# FU6561N-XCQ-DEMO_V1_0-20251116.net
KiCad netlist of a schematic drawn in Altium Designer
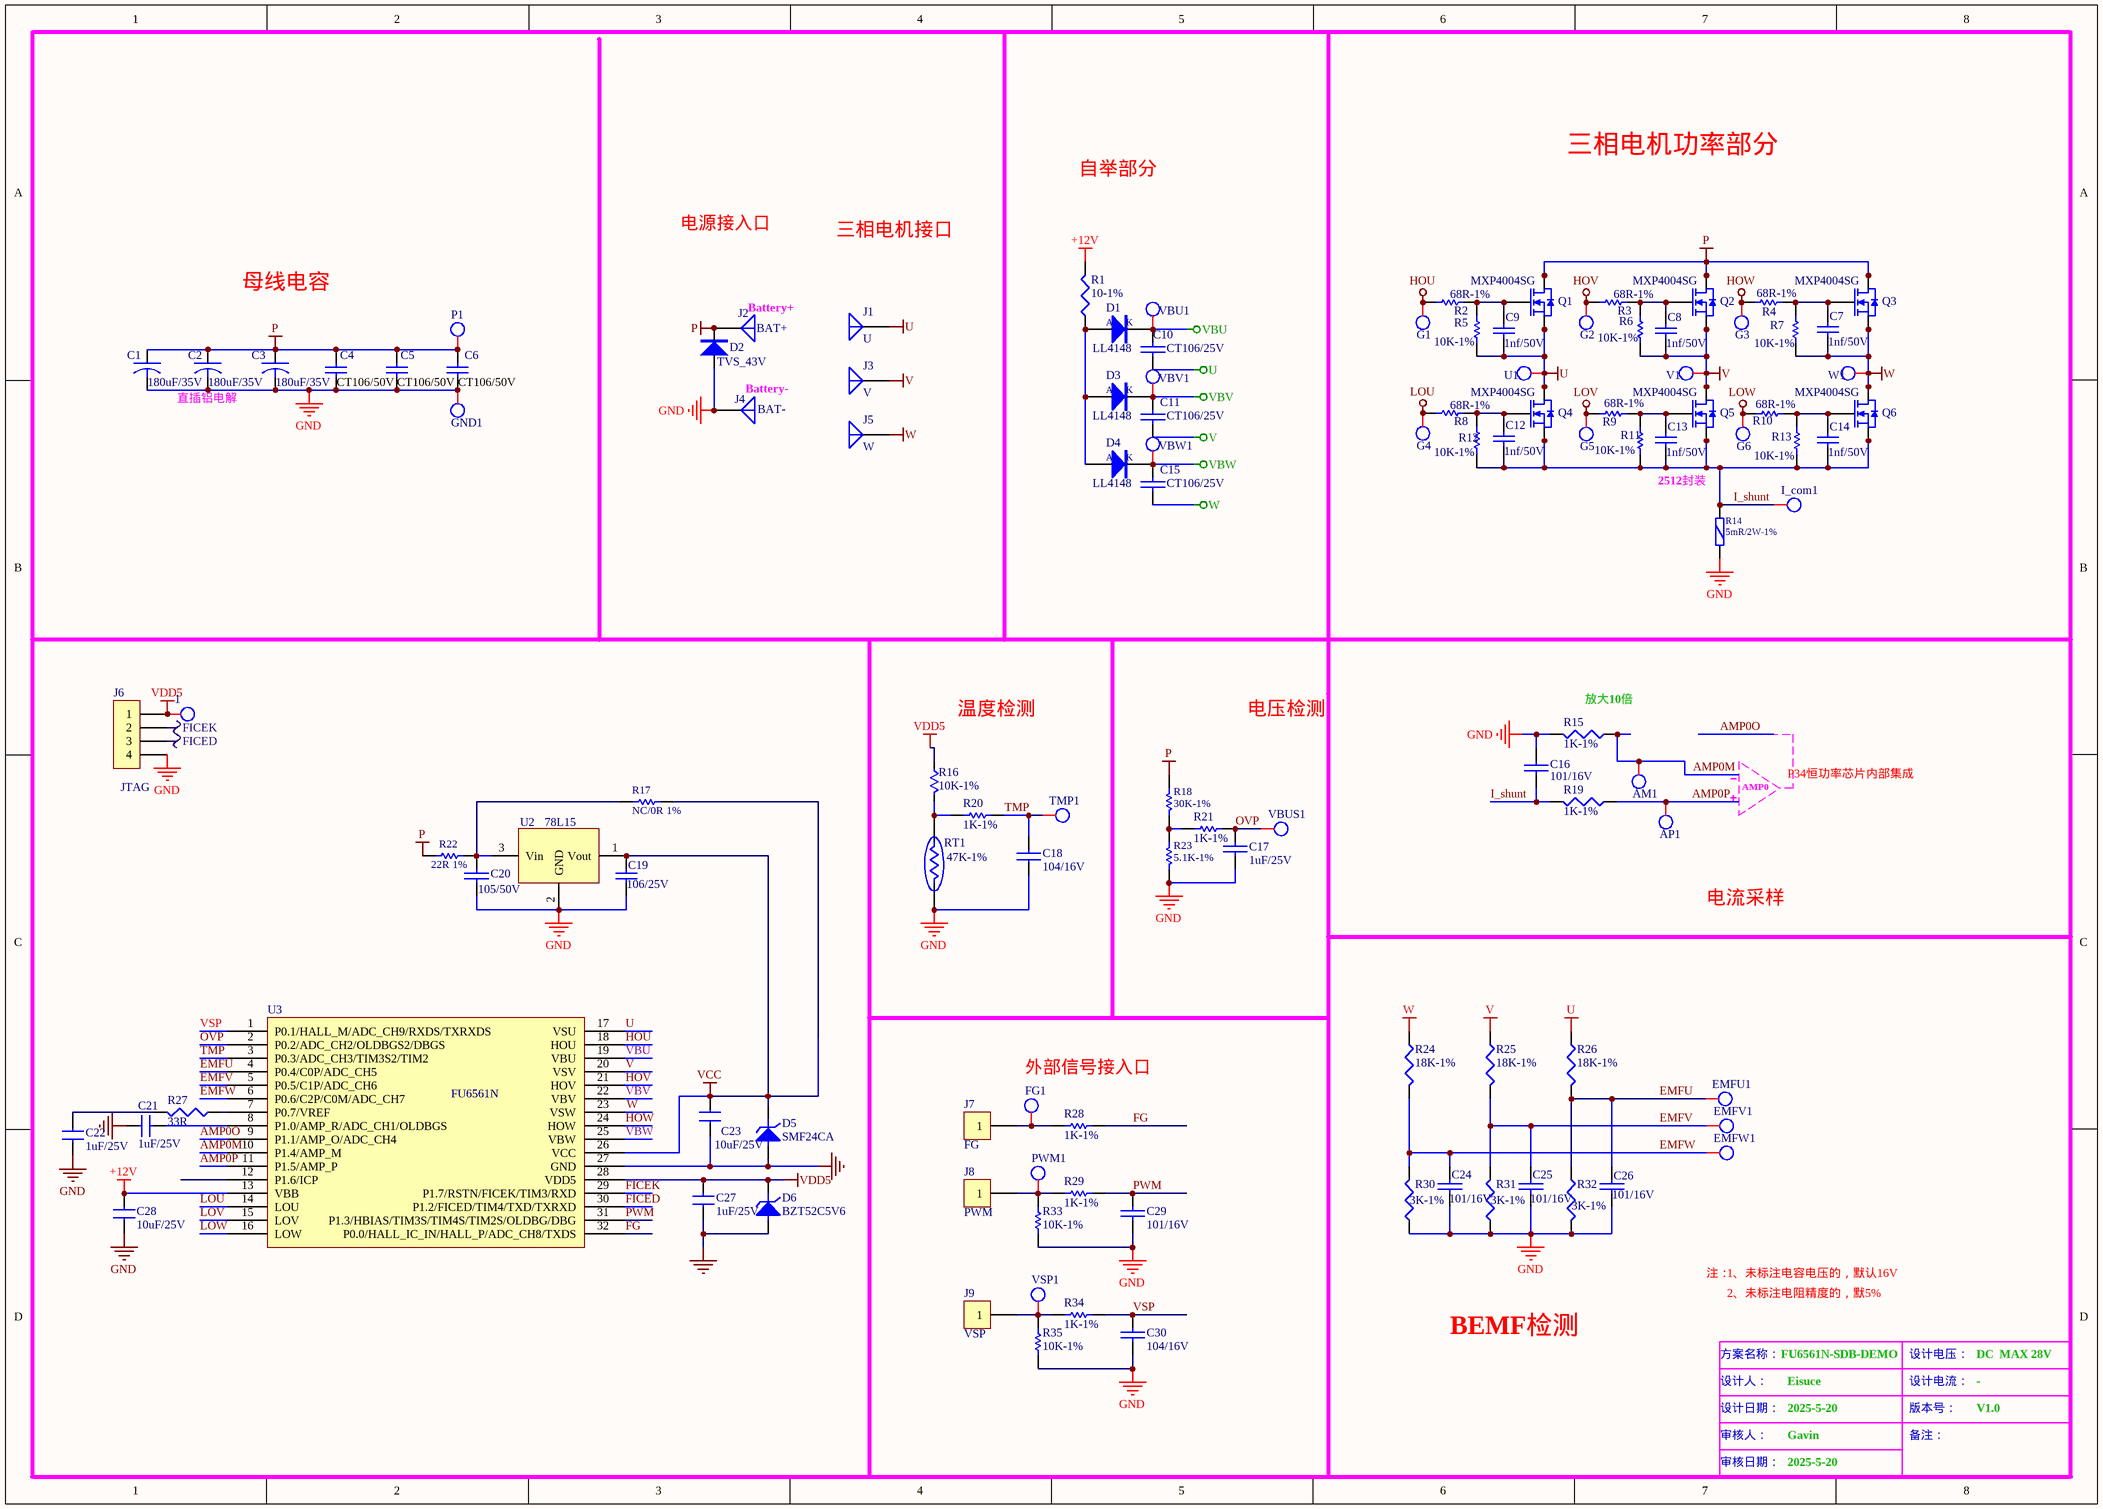
[diagram p0: FU6561N-XCQ-DEMO_V1.0-20251116.SCHDOC]

(export (version "E")
  (design (tool "Eeschema 10.0.6"))
  (components
    (comp (ref "1") (value "~") (footprint "TPM") (libsource (lib "*") (part "Component_1")))
    (comp (ref "AM1") (value "~") (footprint "TPM") (libsource (lib "*") (part "Component_1")))
    (comp (ref "AP1") (value "~") (footprint "TPM") (libsource (lib "*") (part "Component_1")))
    (comp (ref "C1")
      (value "180uF/35V")
      (footprint "CAP2_5")
      (description "Capacitor")
      (libsource (lib "*") (part "CAPACITOR"))
    )
    (comp (ref "C2")
      (value "180uF/35V")
      (footprint "CAP2_5")
      (description "Capacitor")
      (libsource (lib "*") (part "CAPACITOR"))
    )
    (comp (ref "C3")
      (value "180uF/35V")
      (footprint "CAP2_5")
      (description "Capacitor")
      (libsource (lib "*") (part "CAPACITOR"))
    )
    (comp (ref "C4")
      (value "CT106/50V")
      (footprint "c1206")
      (description "YG-C1206K106-50V（10UF）-10%")
      (fields (field (name "PUBLISHER") "Altium Limited"))
      (libsource (lib "*") (part "Cap"))
    )
    (comp (ref "C5")
      (value "CT106/50V")
      (footprint "c1206")
      (description "YG-C1206K106-50V（10UF）-10%")
      (fields (field (name "PUBLISHER") "Altium Limited"))
      (libsource (lib "*") (part "Cap"))
    )
    (comp (ref "C6")
      (value "CT106/50V")
      (footprint "c1206")
      (description "YG-C1206K106-50V（10UF）-10%")
      (fields (field (name "PUBLISHER") "Altium Limited"))
      (libsource (lib "*") (part "Cap"))
    )
    (comp (ref "C7")
      (value "1nf/50V")
      (footprint "c0603")
      (description "YG-C1206K106-50V（10UF）-10%")
      (fields (field (name "PUBLISHER") "Altium Limited"))
      (libsource (lib "*") (part "Cap"))
    )
    (comp (ref "C8")
      (value "1nf/50V")
      (footprint "C0603")
      (description "YG-C1206K106-50V（10UF）-10%")
      (fields (field (name "PUBLISHER") "Altium Limited"))
      (libsource (lib "*") (part "Cap"))
    )
    (comp (ref "C9")
      (value "1nf/50V")
      (footprint "C0603")
      (description "YG-C1206K106-50V（10UF）-10%")
      (fields (field (name "PUBLISHER") "Altium Limited"))
      (libsource (lib "*") (part "Cap"))
    )
    (comp (ref "C10")
      (value "CT106/25V")
      (footprint "c0805")
      (description "Capacitor")
      (libsource (lib "*") (part "CAP-CC(SMD)"))
    )
    (comp (ref "C11")
      (value "CT106/25V")
      (footprint "c0805")
      (description "Capacitor")
      (libsource (lib "*") (part "CAP-CC(SMD)"))
    )
    (comp (ref "C12")
      (value "1nf/50V")
      (footprint "c0603")
      (description "YG-C1206K106-50V（10UF）-10%")
      (fields (field (name "PUBLISHER") "Altium Limited"))
      (libsource (lib "*") (part "Cap"))
    )
    (comp (ref "C13")
      (value "1nf/50V")
      (footprint "C0603")
      (description "YG-C1206K106-50V（10UF）-10%")
      (fields (field (name "PUBLISHER") "Altium Limited"))
      (libsource (lib "*") (part "Cap"))
    )
    (comp (ref "C14")
      (value "1nf/50V")
      (footprint "C0603")
      (description "YG-C1206K106-50V（10UF）-10%")
      (fields (field (name "PUBLISHER") "Altium Limited"))
      (libsource (lib "*") (part "Cap"))
    )
    (comp (ref "C15")
      (value "CT106/25V")
      (footprint "c0805")
      (description "Capacitor")
      (libsource (lib "*") (part "CAP-CC(SMD)"))
    )
    (comp (ref "C16")
      (value "101/16V")
      (footprint "c0603")
      (description "Capacitor")
      (libsource (lib "") (part "CAP_1"))
    )
    (comp (ref "C17")
      (value "1uF/25V")
      (footprint "c0603")
      (description "Capacitor")
      (libsource (lib "") (part "CAP_2"))
    )
    (comp (ref "C18") (value "104/16V") (footprint "c0603") (libsource (lib "*") (part "CAP NP")))
    (comp (ref "C19")
      (value "106/25V")
      (footprint "C0805")
      (description "Capacitor (Semiconductor SIM Model)")
      (fields (field (name "PUBLISHER") "Altium Limited"))
      (libsource (lib "Miscellaneous Devices") (part "Cap Semi"))
    )
    (comp (ref "C20")
      (value "105/50V")
      (footprint "c1206")
      (description "Capacitor")
      (libsource (lib "") (part "CAP_2"))
    )
    (comp (ref "C21")
      (value "1uF/25V")
      (footprint "C0603")
      (description "Capacitor")
      (libsource (lib "*") (part "CAP"))
    )
    (comp (ref "C22")
      (value "1uF/25V")
      (footprint "C0603")
      (description "Capacitor")
      (libsource (lib "*") (part "CAP"))
    )
    (comp (ref "C23")
      (value "10uF/25V")
      (footprint "C0603")
      (description "Capacitor")
      (libsource (lib "*") (part "CAP"))
    )
    (comp (ref "C24")
      (value "101/16V")
      (footprint "c0603")
      (description "Capacitor")
      (libsource (lib "") (part "CAP_1"))
    )
    (comp (ref "C25")
      (value "101/16V")
      (footprint "c0603")
      (description "Capacitor")
      (libsource (lib "") (part "CAP_1"))
    )
    (comp (ref "C26")
      (value "101/16V")
      (footprint "c0603")
      (description "Capacitor")
      (libsource (lib "") (part "CAP_1"))
    )
    (comp (ref "C27")
      (value "1uF/25V")
      (footprint "C0603")
      (description "Capacitor")
      (libsource (lib "*") (part "CAP"))
    )
    (comp (ref "C28")
      (value "10uF/25V")
      (footprint "C0603")
      (description "Capacitor")
      (libsource (lib "*") (part "CAP"))
    )
    (comp (ref "C29")
      (value "101/16V")
      (footprint "c0603")
      (description "Capacitor")
      (libsource (lib "") (part "CAP_2"))
    )
    (comp (ref "C30")
      (value "104/16V")
      (footprint "c0603")
      (description "Capacitor")
      (libsource (lib "") (part "CAP_2"))
    )
    (comp (ref "D1")
      (value "LL4148")
      (footprint "SOD-123")
      (description "Diode")
      (libsource (lib "*") (part "DIODE"))
    )
    (comp (ref "D2") (value "TVS_43V") (footprint "DO214AA, SMB") (libsource (lib "*") (part "D1206")))
    (comp (ref "D3")
      (value "LL4148")
      (footprint "SOD-123")
      (description "Diode")
      (libsource (lib "*") (part "DIODE"))
    )
    (comp (ref "D4")
      (value "LL4148")
      (footprint "SOD-123")
      (description "Diode")
      (libsource (lib "*") (part "DIODE"))
    )
    (comp (ref "D5")
      (value "SMF24CA")
      (footprint "SOD-123")
      (description "Zener Diode")
      (libsource (lib "") (part "TVS1_1"))
    )
    (comp (ref "D6")
      (value "BZT52C5V6")
      (footprint "SOD-123")
      (description "Zener Diode")
      (libsource (lib "*") (part "TVS1"))
    )
    (comp (ref "EMFU1") (value "~") (footprint "TPM") (libsource (lib "*") (part "Component_1")))
    (comp (ref "EMFV1") (value "~") (footprint "TPM") (libsource (lib "*") (part "Component_1")))
    (comp (ref "EMFW1") (value "~") (footprint "TPM") (libsource (lib "*") (part "Component_1")))
    (comp (ref "FG1") (value "~") (footprint "TPM") (libsource (lib "*") (part "Component_1")))
    (comp (ref "G1") (value "~") (footprint "TPM") (libsource (lib "*") (part "Component_1")))
    (comp (ref "G2") (value "~") (footprint "TPM") (libsource (lib "*") (part "Component_1")))
    (comp (ref "G3") (value "~") (footprint "TPM") (libsource (lib "*") (part "Component_1")))
    (comp (ref "G4") (value "~") (footprint "TPM") (libsource (lib "*") (part "Component_1")))
    (comp (ref "G5") (value "~") (footprint "TPM") (libsource (lib "*") (part "Component_1")))
    (comp (ref "G6") (value "~") (footprint "TPM") (libsource (lib "*") (part "Component_1")))
    (comp (ref "GND1") (value "~") (footprint "TPM") (libsource (lib "*") (part "Component_1")))
    (comp (ref "I_com1") (value "~") (footprint "TPM") (libsource (lib "*") (part "Component_1")))
    (comp (ref "J1")
      (value "U")
      (footprint "AD")
      (description "Generic Antenna")
      (libsource (lib "*") (part "ANTENNA"))
    )
    (comp (ref "J2")
      (value "BAT+")
      (footprint "DY")
      (description "Generic Antenna")
      (libsource (lib "") (part "ANTENNA_2"))
    )
    (comp (ref "J3")
      (value "V")
      (footprint "AD")
      (description "Generic Antenna")
      (libsource (lib "") (part "ANTENNA_3"))
    )
    (comp (ref "J4")
      (value "BAT-")
      (footprint "DY")
      (description "Generic Antenna")
      (libsource (lib "") (part "ANTENNA_2"))
    )
    (comp (ref "J5")
      (value "W")
      (footprint "AD")
      (description "Generic Antenna")
      (libsource (lib "") (part "ANTENNA_1"))
    )
    (comp (ref "J6")
      (value "JTAG")
      (footprint "SIP4-2")
      (description "Connector")
      (libsource (lib "*") (part "CON4"))
    )
    (comp (ref "J7")
      (value "FG")
      (footprint "tp")
      (description "Connector")
      (libsource (lib "SCH 常用封装") (part "CON1"))
    )
    (comp (ref "J8")
      (value "PWM")
      (footprint "tp")
      (description "Connector")
      (libsource (lib "SCH 常用封装") (part "CON1"))
    )
    (comp (ref "J9")
      (value "VSP")
      (footprint "tp")
      (description "Connector")
      (libsource (lib "SCH 常用封装") (part "CON1"))
    )
    (comp (ref "P1") (value "~") (footprint "TPM") (libsource (lib "*") (part "Component_1")))
    (comp (ref "PWM1") (value "~") (footprint "TPM") (libsource (lib "*") (part "Component_1")))
    (comp (ref "Q1") (value "MXP4004SG") (footprint "PQFQ5X6") (libsource (lib "*") (part "MOSFET-N")))
    (comp (ref "Q2") (value "MXP4004SG") (footprint "PQFQ5X6") (libsource (lib "*") (part "MOSFET-N")))
    (comp (ref "Q3") (value "MXP4004SG") (footprint "PQFQ5X6") (libsource (lib "*") (part "MOSFET-N")))
    (comp (ref "Q4") (value "MXP4004SG") (footprint "PQFQ5X6") (libsource (lib "*") (part "MOSFET-N")))
    (comp (ref "Q5") (value "MXP4004SG") (footprint "PQFQ5X6") (libsource (lib "*") (part "MOSFET-N")))
    (comp (ref "Q6") (value "MXP4004SG") (footprint "PQFQ5X6") (libsource (lib "*") (part "MOSFET-N")))
    (comp (ref "R1") (value "10-1%") (footprint "r1206") (libsource (lib "*") (part "RES(SMD)")))
    (comp (ref "R2")
      (value "68R-1%")
      (footprint "r0603")
      (description "Semiconductor Resistor")
      (fields (field (name "PUBLISHER") "Altium Limited"))
      (libsource (lib "Miscellaneous Devices") (part "Res Semi"))
    )
    (comp (ref "R3")
      (value "68R-1%")
      (footprint "r0603")
      (description "Semiconductor Resistor")
      (fields (field (name "PUBLISHER") "Altium Limited"))
      (libsource (lib "Miscellaneous Devices") (part "Res Semi"))
    )
    (comp (ref "R4")
      (value "68R-1%")
      (footprint "r0603")
      (description "Semiconductor Resistor")
      (fields (field (name "PUBLISHER") "Altium Limited"))
      (libsource (lib "Miscellaneous Devices") (part "Res Semi"))
    )
    (comp (ref "R5")
      (value "10K-1%")
      (footprint "r0603")
      (description "YG-R0603F2002(20KΩ)-1%")
      (fields (field (name "PUBLISHER") "Altium Limited"))
      (libsource (lib "Miscellaneous Devices") (part "Res Semi"))
    )
    (comp (ref "R6")
      (value "10K-1%")
      (footprint "r0603")
      (description "YG-R0603F2002(20KΩ)-1%")
      (fields (field (name "PUBLISHER") "Altium Limited"))
      (libsource (lib "Miscellaneous Devices") (part "Res Semi"))
    )
    (comp (ref "R7")
      (value "10K-1%")
      (footprint "r0603")
      (description "YG-R0603F2002(20KΩ)-1%")
      (fields (field (name "PUBLISHER") "Altium Limited"))
      (libsource (lib "Miscellaneous Devices") (part "Res Semi"))
    )
    (comp (ref "R8")
      (value "68R-1%")
      (footprint "r0603")
      (description "Semiconductor Resistor")
      (fields (field (name "PUBLISHER") "Altium Limited"))
      (libsource (lib "Miscellaneous Devices") (part "Res Semi"))
    )
    (comp (ref "R9")
      (value "68R-1%")
      (footprint "r0603")
      (description "Semiconductor Resistor")
      (fields (field (name "PUBLISHER") "Altium Limited"))
      (libsource (lib "Miscellaneous Devices") (part "Res Semi"))
    )
    (comp (ref "R10")
      (value "68R-1%")
      (footprint "r0603")
      (description "Semiconductor Resistor")
      (fields (field (name "PUBLISHER") "Altium Limited"))
      (libsource (lib "Miscellaneous Devices") (part "Res Semi"))
    )
    (comp (ref "R11")
      (value "10K-1%")
      (footprint "r0603")
      (description "YG-R0603F2002(20KΩ)-1%")
      (fields (field (name "PUBLISHER") "Altium Limited"))
      (libsource (lib "Miscellaneous Devices") (part "Res Semi"))
    )
    (comp (ref "R12")
      (value "10K-1%")
      (footprint "r0603")
      (description "YG-R0603F2002(20KΩ)-1%")
      (fields (field (name "PUBLISHER") "Altium Limited"))
      (libsource (lib "Miscellaneous Devices") (part "Res Semi"))
    )
    (comp (ref "R13")
      (value "10K-1%")
      (footprint "r0603")
      (description "YG-R0603F2002(20KΩ)-1%")
      (fields (field (name "PUBLISHER") "Altium Limited"))
      (libsource (lib "Miscellaneous Devices") (part "Res Semi"))
    )
    (comp (ref "R14") (value "5mR/2W-1%") (footprint "r2512") (libsource (lib "*") (part "R-RES/2")))
    (comp (ref "R15") (value "1K-1%") (footprint "r0603") (libsource (lib "*") (part "RES(SMD)")))
    (comp (ref "R16") (value "10K-1%") (footprint "r0603") (libsource (lib "*") (part "RES3")))
    (comp (ref "R17")
      (value "NC/0R 1%")
      (footprint "R1206")
      (description "R0603F1001(1KΩ)-1%")
      (fields (field (name "PUBLISHER") "Altium Limited"))
      (libsource (lib "Miscellaneous Devices") (part "res1"))
    )
    (comp (ref "R18")
      (value "30K-1%")
      (footprint "r0603")
      (description "Resistor")
      (fields (field (name "PUBLISHER") "Altium Limited"))
      (libsource (lib "Miscellaneous Devices") (part "res1"))
    )
    (comp (ref "R19") (value "1K-1%") (footprint "r0603") (libsource (lib "*") (part "RES(SMD)")))
    (comp (ref "R20")
      (value "1K-1%")
      (footprint "r0603")
      (description "Semiconductor Resistor")
      (fields (field (name "PUBLISHER") "Altium Limited"))
      (libsource (lib "Miscellaneous Devices") (part "Res Semi"))
    )
    (comp (ref "R21")
      (value "1K-1%")
      (footprint "r0603")
      (description "Semiconductor Resistor")
      (fields (field (name "PUBLISHER") "Altium Limited"))
      (libsource (lib "Miscellaneous Devices") (part "Res Semi"))
    )
    (comp (ref "R22")
      (value "22R 1%")
      (footprint "R1206")
      (description "R0603F1001(1KΩ)-1%")
      (fields (field (name "PUBLISHER") "Altium Limited"))
      (libsource (lib "Miscellaneous Devices") (part "res1"))
    )
    (comp (ref "R23")
      (value "5.1K-1%")
      (footprint "r0603")
      (description "Resistor")
      (fields (field (name "PUBLISHER") "Altium Limited"))
      (libsource (lib "Miscellaneous Devices") (part "res1"))
    )
    (comp (ref "R24") (value "18K-1%") (footprint "r0603") (libsource (lib "*") (part "RES(SMD)")))
    (comp (ref "R25") (value "18K-1%") (footprint "r0603") (libsource (lib "*") (part "RES(SMD)")))
    (comp (ref "R26") (value "18K-1%") (footprint "r0603") (libsource (lib "*") (part "RES(SMD)")))
    (comp (ref "R27") (value "33R") (footprint "R0603") (libsource (lib "*") (part "RES(SMD)")))
    (comp (ref "R28")
      (value "1K-1%")
      (footprint "r0603")
      (description "Semiconductor Resistor")
      (fields (field (name "PUBLISHER") "Altium Limited"))
      (libsource (lib "Miscellaneous Devices") (part "Res Semi"))
    )
    (comp (ref "R29")
      (value "1K-1%")
      (footprint "r0603")
      (description "Semiconductor Resistor")
      (fields (field (name "PUBLISHER") "Altium Limited"))
      (libsource (lib "Miscellaneous Devices") (part "Res Semi"))
    )
    (comp (ref "R30") (value "3K-1%") (footprint "r0603") (libsource (lib "*") (part "RES(SMD)")))
    (comp (ref "R31") (value "3K-1%") (footprint "r0603") (libsource (lib "*") (part "RES(SMD)")))
    (comp (ref "R32") (value "3K-1%") (footprint "r0603") (libsource (lib "*") (part "RES(SMD)")))
    (comp (ref "R33")
      (value "10K-1%")
      (footprint "r0603")
      (description "Semiconductor Resistor")
      (fields (field (name "PUBLISHER") "Altium Limited"))
      (libsource (lib "Miscellaneous Devices") (part "Res Semi"))
    )
    (comp (ref "R34")
      (value "1K-1%")
      (footprint "r0603")
      (description "Semiconductor Resistor")
      (fields (field (name "PUBLISHER") "Altium Limited"))
      (libsource (lib "Miscellaneous Devices") (part "Res Semi"))
    )
    (comp (ref "R35")
      (value "10K-1%")
      (footprint "r0603")
      (description "Semiconductor Resistor")
      (fields (field (name "PUBLISHER") "Altium Limited"))
      (libsource (lib "Miscellaneous Devices") (part "Res Semi"))
    )
    (comp (ref "RT1")
      (value "47K-1%")
      (footprint "r0603")
      (description "Thermistor")
      (fields (field (name "PUBLISHER") "Altium Limited"))
      (libsource (lib "*") (part "Res Thermal"))
    )
    (comp (ref "TMP1") (value "~") (footprint "TPM") (libsource (lib "*") (part "Component_1")))
    (comp (ref "U1") (value "~") (footprint "TPM") (libsource (lib "*") (part "Component_1")))
    (comp (ref "U2")
      (value "78L15")
      (footprint "SOT-89")
      (description "78M12")
      (libsource (lib "*") (part "VOLTREG"))
    )
    (comp (ref "U3")
      (value "FU6561N")
      (footprint "QFN32-0.4-4X4")
      (libsource (lib "SCH 常用封装") (part "FU6561N"))
    )
    (comp (ref "V1") (value "~") (footprint "TPM") (libsource (lib "*") (part "Component_1")))
    (comp (ref "VBU1") (value "~") (footprint "TPM") (libsource (lib "*") (part "Component_1")))
    (comp (ref "VBUS1") (value "~") (footprint "TPM") (libsource (lib "*") (part "Component_1")))
    (comp (ref "VBV1") (value "~") (footprint "TPM") (libsource (lib "*") (part "Component_1")))
    (comp (ref "VBW1") (value "~") (footprint "TPM") (libsource (lib "*") (part "Component_1")))
    (comp (ref "VSP1") (value "~") (footprint "TPM") (libsource (lib "*") (part "Component_1")))
    (comp (ref "W1") (value "~") (footprint "TPM") (libsource (lib "*") (part "Component_1")))
  )
  (nets
    (net (code "1") (name "+12V") (class "Default")
      (node (ref "C28") (pin "1") (pinfunction "1_1") (pintype "passive"))
      (node (ref "R1") (pin "2") (pinfunction "2_2") (pintype "passive"))
      (node (ref "U3") (pin "13") (pinfunction "VBB_13") (pintype "passive"))
    )
    (net (code "2") (name "/AMP0M") (class "Default")
      (node (ref "AM1") (pin "1") (pinfunction "0_1") (pintype "passive"))
      (node (ref "R15") (pin "1") (pinfunction "1_1") (pintype "passive"))
      (node (ref "U3") (pin "10") (pinfunction "P1.4/AMP_M_10") (pintype "passive"))
    )
    (net (code "3") (name "/AMP0O") (class "Default")
      (node (ref "U3") (pin "9") (pinfunction "P1.1/AMP_O/ADC_CH4_9") (pintype "passive"))
    )
    (net (code "4") (name "/AMP0P") (class "Default")
      (node (ref "AP1") (pin "1") (pinfunction "0_1") (pintype "passive"))
      (node (ref "R19") (pin "1") (pinfunction "1_1") (pintype "passive"))
      (node (ref "U3") (pin "11") (pinfunction "P1.5/AMP_P_11") (pintype "passive"))
    )
    (net (code "5") (name "/EMFU") (class "Default")
      (node (ref "C26") (pin "2") (pinfunction "2_2") (pintype "passive"))
      (node (ref "EMFU1") (pin "1") (pinfunction "0_1") (pintype "passive"))
      (node (ref "R26") (pin "2") (pinfunction "2_2") (pintype "passive"))
      (node (ref "R32") (pin "1") (pinfunction "1_1") (pintype "passive"))
      (node (ref "U3") (pin "4") (pinfunction "P0.4/C0P/ADC_CH5_4") (pintype "passive"))
    )
    (net (code "6") (name "/EMFV") (class "Default")
      (node (ref "C25") (pin "1") (pinfunction "1_1") (pintype "passive"))
      (node (ref "EMFV1") (pin "1") (pinfunction "0_1") (pintype "passive"))
      (node (ref "R25") (pin "2") (pinfunction "2_2") (pintype "passive"))
      (node (ref "R31") (pin "2") (pinfunction "2_2") (pintype "passive"))
      (node (ref "U3") (pin "5") (pinfunction "P0.5/C1P/ADC_CH6_5") (pintype "passive"))
    )
    (net (code "7") (name "/EMFW") (class "Default")
      (node (ref "C24") (pin "1") (pinfunction "1_1") (pintype "passive"))
      (node (ref "EMFW1") (pin "1") (pinfunction "0_1") (pintype "passive"))
      (node (ref "R24") (pin "2") (pinfunction "2_2") (pintype "passive"))
      (node (ref "R30") (pin "2") (pinfunction "2_2") (pintype "passive"))
      (node (ref "U3") (pin "6") (pinfunction "P0.6/C2P/C0M/ADC_CH7_6") (pintype "passive"))
    )
    (net (code "8") (name "/FG") (class "Default")
      (node (ref "R28") (pin "2") (pinfunction "2_2") (pintype "passive"))
      (node (ref "U3") (pin "32") (pinfunction "P0.0/HALL_IC_IN/HALL_P/ADC_CH8/TXDS_32") (pintype "passive"))
    )
    (net (code "9") (name "/I_shunt") (class "Default")
      (node (ref "C12") (pin "1") (pinfunction "1_1") (pintype "passive"))
      (node (ref "C13") (pin "1") (pinfunction "1_1") (pintype "passive"))
      (node (ref "C14") (pin "1") (pinfunction "1_1") (pintype "passive"))
      (node (ref "C16") (pin "2") (pinfunction "2_2") (pintype "passive"))
      (node (ref "I_com1") (pin "1") (pinfunction "0_1") (pintype "passive"))
      (node (ref "Q4") (pin "1") (pinfunction "S_1") (pintype "passive"))
      (node (ref "Q4") (pin "2") (pinfunction "S_2") (pintype "passive"))
      (node (ref "Q4") (pin "3") (pinfunction "S_3") (pintype "passive"))
      (node (ref "Q5") (pin "1") (pinfunction "S_1") (pintype "passive"))
      (node (ref "Q5") (pin "2") (pinfunction "S_2") (pintype "passive"))
      (node (ref "Q5") (pin "3") (pinfunction "S_3") (pintype "passive"))
      (node (ref "Q6") (pin "1") (pinfunction "S_1") (pintype "passive"))
      (node (ref "Q6") (pin "2") (pinfunction "S_2") (pintype "passive"))
      (node (ref "Q6") (pin "3") (pinfunction "S_3") (pintype "passive"))
      (node (ref "R11") (pin "1") (pinfunction "1_1") (pintype "passive"))
      (node (ref "R12") (pin "1") (pinfunction "1_1") (pintype "passive"))
      (node (ref "R13") (pin "1") (pinfunction "1_1") (pintype "passive"))
      (node (ref "R14") (pin "2") (pinfunction "2_2") (pintype "passive"))
      (node (ref "R19") (pin "2") (pinfunction "2_2") (pintype "passive"))
    )
    (net (code "10") (name "/OVP") (class "Default")
      (node (ref "C17") (pin "1") (pinfunction "1_1") (pintype "passive"))
      (node (ref "R21") (pin "2") (pinfunction "2_2") (pintype "passive"))
      (node (ref "U3") (pin "2") (pinfunction "P0.2/ADC_CH2/OLDBGS2/DBGS_2") (pintype "passive"))
      (node (ref "VBUS1") (pin "1") (pinfunction "0_1") (pintype "passive"))
    )
    (net (code "12") (name "/PWM") (class "Default")
      (node (ref "C29") (pin "2") (pinfunction "2_2") (pintype "passive"))
      (node (ref "R29") (pin "2") (pinfunction "2_2") (pintype "passive"))
      (node (ref "U3") (pin "31") (pinfunction "P1.3/HBIAS/TIM3S/TIM4S/TIM2S/OLDBG/DBG_31") (pintype "passive"))
    )
    (net (code "13") (name "/TMP") (class "Default")
      (node (ref "C18") (pin "2") (pinfunction "2_2") (pintype "passive"))
      (node (ref "R20") (pin "2") (pinfunction "2_2") (pintype "passive"))
      (node (ref "TMP1") (pin "1") (pinfunction "0_1") (pintype "passive"))
      (node (ref "U3") (pin "3") (pinfunction "P0.3/ADC_CH3/TIM3S2/TIM2_3") (pintype "passive"))
    )
    (net (code "14") (name "/VSP") (class "Default")
      (node (ref "C30") (pin "2") (pinfunction "2_2") (pintype "passive"))
      (node (ref "R34") (pin "2") (pinfunction "2_2") (pintype "passive"))
      (node (ref "U3") (pin "1") (pinfunction "P0.1/HALL_M/ADC_CH9/RXDS/TXRXDS_1") (pintype "passive"))
    )
    (net (code "15") (name "FICED") (class "Default")
      (node (ref "J6") (pin "3") (pinfunction "3_3") (pintype "passive"))
      (node (ref "U3") (pin "30") (pinfunction "P1.2/FICED/TIM4/TXD/TXRXD_30") (pintype "passive"))
    )
    (net (code "16") (name "FICEK") (class "Default")
      (node (ref "J6") (pin "2") (pinfunction "2_2") (pintype "passive"))
      (node (ref "U3") (pin "29") (pinfunction "P1.7/RSTN/FICEK/TIM3/RXD_29") (pintype "passive"))
    )
    (net (code "17") (name "GND") (class "Default")
      (node (ref "C1") (pin "2") (pinfunction "2_2") (pintype "passive"))
      (node (ref "C16") (pin "1") (pinfunction "1_1") (pintype "passive"))
      (node (ref "C17") (pin "2") (pinfunction "2_2") (pintype "passive"))
      (node (ref "C18") (pin "1") (pinfunction "1_1") (pintype "passive"))
      (node (ref "C19") (pin "1") (pinfunction "1_1") (pintype "passive"))
      (node (ref "C2") (pin "2") (pinfunction "2_2") (pintype "passive"))
      (node (ref "C20") (pin "2") (pinfunction "2_2") (pintype "passive"))
      (node (ref "C21") (pin "1") (pinfunction "1_1") (pintype "passive"))
      (node (ref "C22") (pin "1") (pinfunction "1_1") (pintype "passive"))
      (node (ref "C23") (pin "2") (pinfunction "2_2") (pintype "passive"))
      (node (ref "C24") (pin "2") (pinfunction "2_2") (pintype "passive"))
      (node (ref "C25") (pin "2") (pinfunction "2_2") (pintype "passive"))
      (node (ref "C26") (pin "1") (pinfunction "1_1") (pintype "passive"))
      (node (ref "C27") (pin "2") (pinfunction "2_2") (pintype "passive"))
      (node (ref "C28") (pin "2") (pinfunction "2_2") (pintype "passive"))
      (node (ref "C29") (pin "1") (pinfunction "1_1") (pintype "passive"))
      (node (ref "C3") (pin "2") (pinfunction "2_2") (pintype "passive"))
      (node (ref "C30") (pin "1") (pinfunction "1_1") (pintype "passive"))
      (node (ref "C4") (pin "1") (pinfunction "1_1") (pintype "passive"))
      (node (ref "C5") (pin "1") (pinfunction "1_1") (pintype "passive"))
      (node (ref "C6") (pin "1") (pinfunction "1_1") (pintype "passive"))
      (node (ref "D2") (pin "2") (pinfunction "2_2") (pintype "passive"))
      (node (ref "D5") (pin "1") (pinfunction "A_1") (pintype "passive"))
      (node (ref "D6") (pin "1") (pinfunction "A_1") (pintype "passive"))
      (node (ref "GND1") (pin "1") (pinfunction "0_1") (pintype "passive"))
      (node (ref "J4") (pin "1") (pinfunction "+42V_1") (pintype "passive"))
      (node (ref "J6") (pin "4") (pinfunction "4_4") (pintype "passive"))
      (node (ref "R14") (pin "1") (pinfunction "1_1") (pintype "passive"))
      (node (ref "R15") (pin "2") (pinfunction "2_2") (pintype "passive"))
      (node (ref "R23") (pin "2") (pinfunction "2_2") (pintype "passive"))
      (node (ref "R30") (pin "1") (pinfunction "1_1") (pintype "passive"))
      (node (ref "R31") (pin "1") (pinfunction "1_1") (pintype "passive"))
      (node (ref "R32") (pin "2") (pinfunction "2_2") (pintype "passive"))
      (node (ref "R33") (pin "1") (pinfunction "1_1") (pintype "passive"))
      (node (ref "R35") (pin "1") (pinfunction "1_1") (pintype "passive"))
      (node (ref "RT1") (pin "2") (pinfunction "2_2") (pintype "passive"))
      (node (ref "U2") (pin "2") (pinfunction "GND_2") (pintype "passive"))
      (node (ref "U3") (pin "27") (pinfunction "GND_27") (pintype "passive"))
    )
    (net (code "18") (name "HOU") (class "Default")
      (node (ref "G1") (pin "1") (pinfunction "0_1") (pintype "passive"))
      (node (ref "R2") (pin "1") (pinfunction "1_1") (pintype "passive"))
      (node (ref "U3") (pin "18") (pinfunction "HOU_18") (pintype "passive"))
    )
    (net (code "19") (name "HOV") (class "Default")
      (node (ref "G2") (pin "1") (pinfunction "0_1") (pintype "passive"))
      (node (ref "R3") (pin "1") (pinfunction "1_1") (pintype "passive"))
      (node (ref "U3") (pin "21") (pinfunction "HOV_21") (pintype "passive"))
    )
    (net (code "20") (name "HOW") (class "Default")
      (node (ref "G3") (pin "1") (pinfunction "0_1") (pintype "passive"))
      (node (ref "R4") (pin "1") (pinfunction "1_1") (pintype "passive"))
      (node (ref "U3") (pin "24") (pinfunction "HOW_24") (pintype "passive"))
    )
    (net (code "21") (name "LOU") (class "Default")
      (node (ref "G4") (pin "1") (pinfunction "0_1") (pintype "passive"))
      (node (ref "R8") (pin "1") (pinfunction "1_1") (pintype "passive"))
      (node (ref "U3") (pin "14") (pinfunction "LOU_14") (pintype "passive"))
    )
    (net (code "22") (name "LOV") (class "Default")
      (node (ref "G5") (pin "1") (pinfunction "0_1") (pintype "passive"))
      (node (ref "R9") (pin "1") (pinfunction "1_1") (pintype "passive"))
      (node (ref "U3") (pin "15") (pinfunction "LOV_15") (pintype "passive"))
    )
    (net (code "23") (name "LOW") (class "Default")
      (node (ref "G6") (pin "1") (pinfunction "0_1") (pintype "passive"))
      (node (ref "R10") (pin "1") (pinfunction "1_1") (pintype "passive"))
      (node (ref "U3") (pin "16") (pinfunction "LOW_16") (pintype "passive"))
    )
    (net (code "24") (name "Net-(C22-Pad2)") (class "Default")
      (node (ref "C22") (pin "2") (pinfunction "2_2") (pintype "passive"))
      (node (ref "R27") (pin "2") (pinfunction "2_2") (pintype "passive"))
    )
    (net (code "25") (name "Net-(D1-Pad1)") (class "Default")
      (node (ref "D1") (pin "1") (pinfunction "1_1") (pintype "passive"))
      (node (ref "D3") (pin "1") (pinfunction "1_1") (pintype "passive"))
      (node (ref "D4") (pin "1") (pinfunction "1_1") (pintype "passive"))
      (node (ref "R1") (pin "1") (pinfunction "1_1") (pintype "passive"))
    )
    (net (code "26") (name "Net-(FG1-0)") (class "Default")
      (node (ref "FG1") (pin "1") (pinfunction "0_1") (pintype "passive"))
      (node (ref "J7") (pin "1") (pinfunction "1_1") (pintype "passive"))
      (node (ref "R28") (pin "1") (pinfunction "1_1") (pintype "passive"))
    )
    (net (code "27") (name "Net-(PWM1-0)") (class "Default")
      (node (ref "J8") (pin "1") (pinfunction "1_1") (pintype "passive"))
      (node (ref "PWM1") (pin "1") (pinfunction "0_1") (pintype "passive"))
      (node (ref "R29") (pin "1") (pinfunction "1_1") (pintype "passive"))
      (node (ref "R33") (pin "2") (pinfunction "2_2") (pintype "passive"))
    )
    (net (code "28") (name "Net-(Q1-G)") (class "Default")
      (node (ref "C9") (pin "2") (pinfunction "2_2") (pintype "passive"))
      (node (ref "Q1") (pin "4") (pinfunction "G_4") (pintype "passive"))
      (node (ref "R2") (pin "2") (pinfunction "2_2") (pintype "passive"))
      (node (ref "R5") (pin "2") (pinfunction "2_2") (pintype "passive"))
    )
    (net (code "29") (name "Net-(Q2-G)") (class "Default")
      (node (ref "C8") (pin "2") (pinfunction "2_2") (pintype "passive"))
      (node (ref "Q2") (pin "4") (pinfunction "G_4") (pintype "passive"))
      (node (ref "R3") (pin "2") (pinfunction "2_2") (pintype "passive"))
      (node (ref "R6") (pin "2") (pinfunction "2_2") (pintype "passive"))
    )
    (net (code "30") (name "Net-(Q3-G)") (class "Default")
      (node (ref "C7") (pin "2") (pinfunction "2_2") (pintype "passive"))
      (node (ref "Q3") (pin "4") (pinfunction "G_4") (pintype "passive"))
      (node (ref "R4") (pin "2") (pinfunction "2_2") (pintype "passive"))
      (node (ref "R7") (pin "2") (pinfunction "2_2") (pintype "passive"))
    )
    (net (code "31") (name "Net-(Q4-G)") (class "Default")
      (node (ref "C12") (pin "2") (pinfunction "2_2") (pintype "passive"))
      (node (ref "Q4") (pin "4") (pinfunction "G_4") (pintype "passive"))
      (node (ref "R12") (pin "2") (pinfunction "2_2") (pintype "passive"))
      (node (ref "R8") (pin "2") (pinfunction "2_2") (pintype "passive"))
    )
    (net (code "32") (name "Net-(Q5-G)") (class "Default")
      (node (ref "C13") (pin "2") (pinfunction "2_2") (pintype "passive"))
      (node (ref "Q5") (pin "4") (pinfunction "G_4") (pintype "passive"))
      (node (ref "R11") (pin "2") (pinfunction "2_2") (pintype "passive"))
      (node (ref "R9") (pin "2") (pinfunction "2_2") (pintype "passive"))
    )
    (net (code "33") (name "Net-(Q6-G)") (class "Default")
      (node (ref "C14") (pin "2") (pinfunction "2_2") (pintype "passive"))
      (node (ref "Q6") (pin "4") (pinfunction "G_4") (pintype "passive"))
      (node (ref "R10") (pin "2") (pinfunction "2_2") (pintype "passive"))
      (node (ref "R13") (pin "2") (pinfunction "2_2") (pintype "passive"))
    )
    (net (code "34") (name "Net-(R16-Pad2)") (class "Default")
      (node (ref "R16") (pin "2") (pintype "passive"))
      (node (ref "R20") (pin "1") (pinfunction "1_1") (pintype "passive"))
      (node (ref "RT1") (pin "1") (pinfunction "1_1") (pintype "passive"))
    )
    (net (code "35") (name "Net-(R18-Pad2)") (class "Default")
      (node (ref "R18") (pin "2") (pinfunction "2_2") (pintype "passive"))
      (node (ref "R21") (pin "1") (pinfunction "1_1") (pintype "passive"))
      (node (ref "R23") (pin "1") (pinfunction "1_1") (pintype "passive"))
    )
    (net (code "36") (name "Net-(U2-Vin)") (class "Default")
      (node (ref "C20") (pin "1") (pinfunction "1_1") (pintype "passive"))
      (node (ref "R17") (pin "2") (pinfunction "2_2") (pintype "passive"))
      (node (ref "R22") (pin "2") (pinfunction "2_2") (pintype "passive"))
      (node (ref "U2") (pin "3") (pinfunction "Vin_3") (pintype "passive"))
    )
    (net (code "37") (name "Net-(U3-P0.7{slash}VREF)") (class "Default")
      (node (ref "R27") (pin "1") (pinfunction "1_1") (pintype "passive"))
      (node (ref "U3") (pin "7") (pinfunction "P0.7/VREF_7") (pintype "passive"))
    )
    (net (code "38") (name "Net-(U3-P1.0{slash}AMP_R{slash}ADC_CH1{slash}OLDBGS)") (class "Default")
      (node (ref "C21") (pin "2") (pinfunction "2_2") (pintype "passive"))
      (node (ref "U3") (pin "8") (pinfunction "P1.0/AMP_R/ADC_CH1/OLDBGS_8") (pintype "passive"))
    )
    (net (code "39") (name "Net-(VSP1-0)") (class "Default")
      (node (ref "J9") (pin "1") (pinfunction "1_1") (pintype "passive"))
      (node (ref "R34") (pin "1") (pinfunction "1_1") (pintype "passive"))
      (node (ref "R35") (pin "2") (pinfunction "2_2") (pintype "passive"))
      (node (ref "VSP1") (pin "1") (pinfunction "0_1") (pintype "passive"))
    )
    (net (code "40") (name "P") (class "Default")
      (node (ref "C1") (pin "1") (pinfunction "1_1") (pintype "passive"))
      (node (ref "C2") (pin "1") (pinfunction "1_1") (pintype "passive"))
      (node (ref "C3") (pin "1") (pinfunction "1_1") (pintype "passive"))
      (node (ref "C4") (pin "2") (pinfunction "2_2") (pintype "passive"))
      (node (ref "C5") (pin "2") (pinfunction "2_2") (pintype "passive"))
      (node (ref "C6") (pin "2") (pinfunction "2_2") (pintype "passive"))
      (node (ref "D2") (pin "1") (pinfunction "1_1") (pintype "passive"))
      (node (ref "J2") (pin "1") (pinfunction "+42V_1") (pintype "passive"))
      (node (ref "P1") (pin "1") (pinfunction "0_1") (pintype "passive"))
      (node (ref "Q1") (pin "5") (pinfunction "D_5") (pintype "passive"))
      (node (ref "Q1") (pin "6") (pinfunction "D_6") (pintype "passive"))
      (node (ref "Q1") (pin "7") (pinfunction "D_7") (pintype "passive"))
      (node (ref "Q1") (pin "8") (pinfunction "D_8") (pintype "passive"))
      (node (ref "Q2") (pin "5") (pinfunction "D_5") (pintype "passive"))
      (node (ref "Q2") (pin "6") (pinfunction "D_6") (pintype "passive"))
      (node (ref "Q2") (pin "7") (pinfunction "D_7") (pintype "passive"))
      (node (ref "Q2") (pin "8") (pinfunction "D_8") (pintype "passive"))
      (node (ref "Q3") (pin "5") (pinfunction "D_5") (pintype "passive"))
      (node (ref "Q3") (pin "6") (pinfunction "D_6") (pintype "passive"))
      (node (ref "Q3") (pin "7") (pinfunction "D_7") (pintype "passive"))
      (node (ref "Q3") (pin "8") (pinfunction "D_8") (pintype "passive"))
      (node (ref "R18") (pin "1") (pinfunction "1_1") (pintype "passive"))
      (node (ref "R22") (pin "1") (pinfunction "1_1") (pintype "passive"))
    )
    (net (code "41") (name "U") (class "Default")
      (node (ref "C10") (pin "1") (pinfunction "1_1") (pintype "passive"))
      (node (ref "C9") (pin "1") (pinfunction "1_1") (pintype "passive"))
      (node (ref "J1") (pin "1") (pinfunction "U_1") (pintype "passive"))
      (node (ref "Q1") (pin "1") (pinfunction "S_1") (pintype "passive"))
      (node (ref "Q1") (pin "2") (pinfunction "S_2") (pintype "passive"))
      (node (ref "Q1") (pin "3") (pinfunction "S_3") (pintype "passive"))
      (node (ref "Q4") (pin "5") (pinfunction "D_5") (pintype "passive"))
      (node (ref "Q4") (pin "6") (pinfunction "D_6") (pintype "passive"))
      (node (ref "Q4") (pin "7") (pinfunction "D_7") (pintype "passive"))
      (node (ref "Q4") (pin "8") (pinfunction "D_8") (pintype "passive"))
      (node (ref "R26") (pin "1") (pinfunction "1_1") (pintype "passive"))
      (node (ref "R5") (pin "1") (pinfunction "1_1") (pintype "passive"))
      (node (ref "U1") (pin "1") (pinfunction "0_1") (pintype "passive"))
      (node (ref "U3") (pin "17") (pinfunction "VSU_17") (pintype "passive"))
    )
    (net (code "42") (name "V") (class "Default")
      (node (ref "C11") (pin "1") (pinfunction "1_1") (pintype "passive"))
      (node (ref "C8") (pin "1") (pinfunction "1_1") (pintype "passive"))
      (node (ref "J3") (pin "1") (pinfunction "V_1") (pintype "passive"))
      (node (ref "Q2") (pin "1") (pinfunction "S_1") (pintype "passive"))
      (node (ref "Q2") (pin "2") (pinfunction "S_2") (pintype "passive"))
      (node (ref "Q2") (pin "3") (pinfunction "S_3") (pintype "passive"))
      (node (ref "Q5") (pin "5") (pinfunction "D_5") (pintype "passive"))
      (node (ref "Q5") (pin "6") (pinfunction "D_6") (pintype "passive"))
      (node (ref "Q5") (pin "7") (pinfunction "D_7") (pintype "passive"))
      (node (ref "Q5") (pin "8") (pinfunction "D_8") (pintype "passive"))
      (node (ref "R25") (pin "1") (pinfunction "1_1") (pintype "passive"))
      (node (ref "R6") (pin "1") (pinfunction "1_1") (pintype "passive"))
      (node (ref "U3") (pin "20") (pinfunction "VSV_20") (pintype "passive"))
      (node (ref "V1") (pin "1") (pinfunction "0_1") (pintype "passive"))
    )
    (net (code "43") (name "VBU") (class "Default")
      (node (ref "C10") (pin "2") (pinfunction "2_2") (pintype "passive"))
      (node (ref "D1") (pin "2") (pinfunction "2_2") (pintype "passive"))
      (node (ref "U3") (pin "19") (pinfunction "VBU_19") (pintype "passive"))
      (node (ref "VBU1") (pin "1") (pinfunction "0_1") (pintype "passive"))
    )
    (net (code "44") (name "VBV") (class "Default")
      (node (ref "C11") (pin "2") (pinfunction "2_2") (pintype "passive"))
      (node (ref "D3") (pin "2") (pinfunction "2_2") (pintype "passive"))
      (node (ref "U3") (pin "22") (pinfunction "VBV_22") (pintype "passive"))
      (node (ref "VBV1") (pin "1") (pinfunction "0_1") (pintype "passive"))
    )
    (net (code "45") (name "VBW") (class "Default")
      (node (ref "C15") (pin "2") (pinfunction "2_2") (pintype "passive"))
      (node (ref "D4") (pin "2") (pinfunction "2_2") (pintype "passive"))
      (node (ref "U3") (pin "25") (pinfunction "VBW_25") (pintype "passive"))
      (node (ref "VBW1") (pin "1") (pinfunction "0_1") (pintype "passive"))
    )
    (net (code "46") (name "VCC") (class "Default")
      (node (ref "C19") (pin "2") (pinfunction "2_2") (pintype "passive"))
      (node (ref "C23") (pin "1") (pinfunction "1_1") (pintype "passive"))
      (node (ref "D5") (pin "2") (pinfunction "K_2") (pintype "passive"))
      (node (ref "R17") (pin "1") (pinfunction "1_1") (pintype "passive"))
      (node (ref "U2") (pin "1") (pinfunction "Vout_1") (pintype "passive"))
      (node (ref "U3") (pin "26") (pinfunction "VCC_26") (pintype "passive"))
    )
    (net (code "47") (name "VDD5") (class "Default")
      (node (ref "1") (pin "1") (pinfunction "0_1") (pintype "passive"))
      (node (ref "C27") (pin "1") (pinfunction "1_1") (pintype "passive"))
      (node (ref "D6") (pin "2") (pinfunction "K_2") (pintype "passive"))
      (node (ref "J6") (pin "1") (pinfunction "1_1") (pintype "passive"))
      (node (ref "R16") (pin "1") (pintype "passive"))
      (node (ref "U3") (pin "28") (pinfunction "VDD5_28") (pintype "passive"))
    )
    (net (code "48") (name "W") (class "Default")
      (node (ref "C15") (pin "1") (pinfunction "1_1") (pintype "passive"))
      (node (ref "C7") (pin "1") (pinfunction "1_1") (pintype "passive"))
      (node (ref "J5") (pin "1") (pinfunction "W_1") (pintype "passive"))
      (node (ref "Q3") (pin "1") (pinfunction "S_1") (pintype "passive"))
      (node (ref "Q3") (pin "2") (pinfunction "S_2") (pintype "passive"))
      (node (ref "Q3") (pin "3") (pinfunction "S_3") (pintype "passive"))
      (node (ref "Q6") (pin "5") (pinfunction "D_5") (pintype "passive"))
      (node (ref "Q6") (pin "6") (pinfunction "D_6") (pintype "passive"))
      (node (ref "Q6") (pin "7") (pinfunction "D_7") (pintype "passive"))
      (node (ref "Q6") (pin "8") (pinfunction "D_8") (pintype "passive"))
      (node (ref "R24") (pin "1") (pinfunction "1_1") (pintype "passive"))
      (node (ref "R7") (pin "1") (pinfunction "1_1") (pintype "passive"))
      (node (ref "U3") (pin "23") (pinfunction "VSW_23") (pintype "passive"))
      (node (ref "W1") (pin "1") (pinfunction "0_1") (pintype "passive"))
    )
    (net (code "49") (name "unconnected-(U3-P1.6{slash}ICP-Pad12)") (class "Default")
      (node (ref "U3") (pin "12") (pinfunction "P1.6/ICP_12") (pintype "passive"))
    )
  )
)
